# htu20df.net
KiCad netlist of a schematic drawn in EAGLE
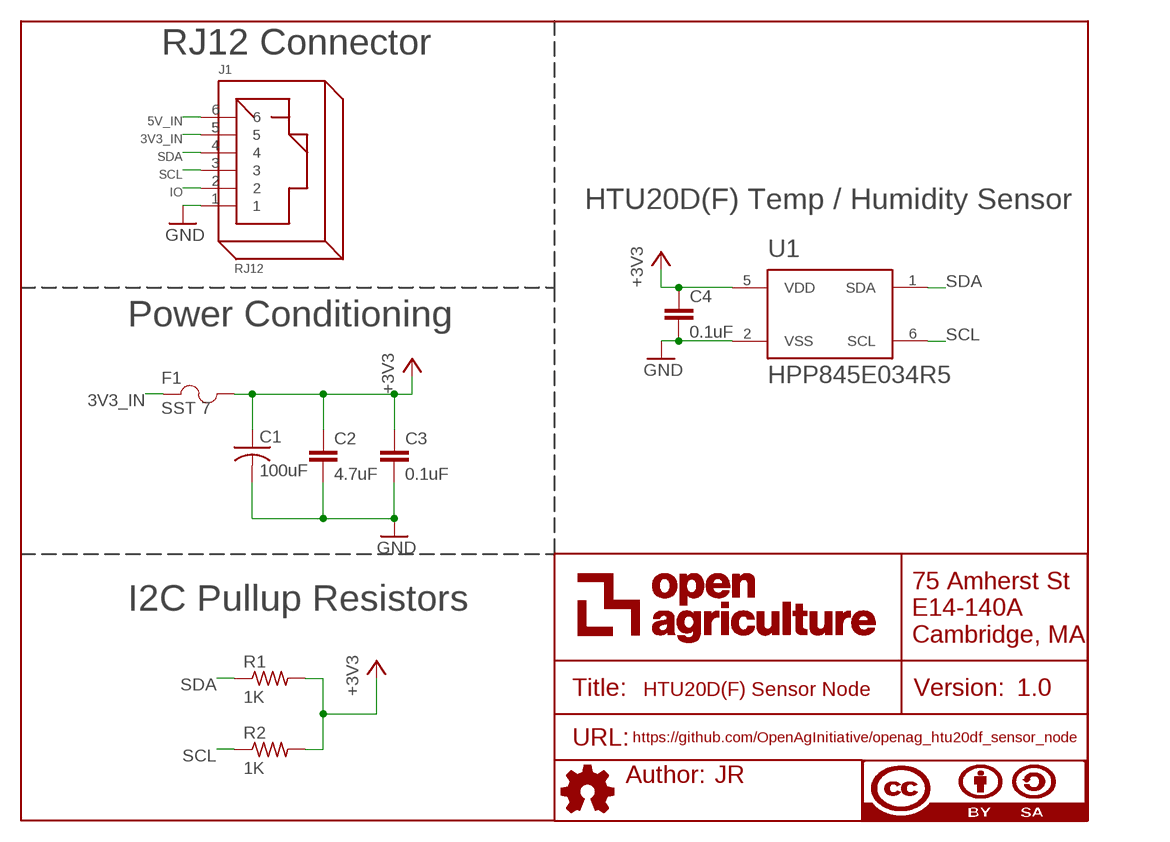
[diagram p0: schematic, sheet 1]

(export (version "E")
  (design (tool "Eeschema 10.0.6"))
  (components
    (comp (ref "C1")
      (value "100uF")
      (footprint "eagle-import:EEE-1HA101UP")
      (libsource (lib "eagle-import") (part "100UF-EEE-1HA101UP"))
    )
    (comp (ref "C2")
      (value "4.7uF")
      (footprint "eagle-import:C0805")
      (libsource (lib "eagle-import") (part "4.7UF-CL21A475KBQNNNE"))
    )
    (comp (ref "C3")
      (value "0.1uF")
      (footprint "eagle-import:C0603")
      (libsource (lib "eagle-import") (part "0.1UF-C0603C104K5RACTU"))
    )
    (comp (ref "C4")
      (value "0.1uF")
      (footprint "eagle-import:C0603")
      (libsource (lib "eagle-import") (part "0.1UF-C0603C104K5RACTU"))
    )
    (comp (ref "F1")
      (value "SST 7")
      (footprint "eagle-import:SS")
      (libsource (lib "eagle-import") (part "SST_7"))
    )
    (comp (ref "FRAME1")
      (value "DOCFIELD")
      (footprint "eagle-import:DOCFIELD")
      (fields
        (field (name "TITLE") "Example Template")
        (field (name "AUTHOR") "XX")
        (field (name "VER") "1.0")
        (field (name "URL") "https://github.com/OpenAgInitiative/openag_eagle_template")
        (field (name "AUTHOR_1") "JR")
        (field (name "TITLE_1") "HTU20D(F) Sensor Node")
        (field (name "URL_1") "https://github.com/OpenAgInitiative/openag_htu20df_sensor_node")
      )
      (libsource (lib "eagle-import") (part "DOCFIELD"))
    )
    (comp (ref "J1")
      (value "RJ12")
      (footprint "eagle-import:RJ12")
      (libsource (lib "eagle-import") (part "A-2004-1-4-LP-N-R"))
    )
    (comp (ref "R1")
      (value "1K")
      (footprint "eagle-import:RC0603N")
      (libsource (lib "eagle-import") (part "1K-ERJ-PB3D1001V"))
    )
    (comp (ref "R2")
      (value "1K")
      (footprint "eagle-import:RC0603N")
      (libsource (lib "eagle-import") (part "1K-ERJ-PB3D1001V"))
    )
    (comp (ref "U1")
      (value "HPP845E034R5")
      (footprint "eagle-import:HTU20D(F)")
      (libsource (lib "eagle-import") (part "HPP845E034R5"))
    )
  )
  (nets
    (net (code "1") (name "+3V3") (class "Default")
      (node (ref "C1") (pin "+") (pinfunction "1(+)_+") (pintype "passive"))
      (node (ref "C2") (pin "1") (pinfunction "1_1") (pintype "passive"))
      (node (ref "C3") (pin "1") (pinfunction "1_1") (pintype "passive"))
      (node (ref "C4") (pin "1") (pinfunction "1_1") (pintype "passive"))
      (node (ref "F1") (pin "2") (pinfunction "2_2") (pintype "passive"))
      (node (ref "R1") (pin "2") (pinfunction "2_2") (pintype "passive"))
      (node (ref "R2") (pin "2") (pinfunction "2_2") (pintype "passive"))
      (node (ref "U1") (pin "5") (pinfunction "VDD_5") (pintype "power_in"))
    )
    (net (code "2") (name "3V3_IN") (class "Default")
      (node (ref "F1") (pin "1") (pinfunction "1_1") (pintype "passive"))
      (node (ref "J1") (pin "5") (pinfunction "5_5") (pintype "bidirectional"))
    )
    (net (code "3") (name "5V_IN") (class "Default")
      (node (ref "J1") (pin "6") (pinfunction "6_6") (pintype "bidirectional"))
    )
    (net (code "4") (name "GND") (class "Default")
      (node (ref "C1") (pin "-") (pinfunction "2(-)_-") (pintype "passive"))
      (node (ref "C2") (pin "2") (pinfunction "2_2") (pintype "passive"))
      (node (ref "C3") (pin "2") (pinfunction "2_2") (pintype "passive"))
      (node (ref "C4") (pin "2") (pinfunction "2_2") (pintype "passive"))
      (node (ref "J1") (pin "1") (pinfunction "1_1") (pintype "bidirectional"))
      (node (ref "U1") (pin "2") (pinfunction "VSS_2") (pintype "power_in"))
    )
    (net (code "5") (name "IO") (class "Default")
      (node (ref "J1") (pin "2") (pinfunction "2_2") (pintype "bidirectional"))
    )
    (net (code "6") (name "SCL") (class "Default")
      (node (ref "J1") (pin "3") (pinfunction "3_3") (pintype "bidirectional"))
      (node (ref "R2") (pin "1") (pinfunction "1_1") (pintype "passive"))
      (node (ref "U1") (pin "6") (pinfunction "SCL_6") (pintype "bidirectional"))
    )
    (net (code "7") (name "SDA") (class "Default")
      (node (ref "J1") (pin "4") (pinfunction "4_4") (pintype "bidirectional"))
      (node (ref "R1") (pin "1") (pinfunction "1_1") (pintype "passive"))
      (node (ref "U1") (pin "1") (pinfunction "SDA_1") (pintype "bidirectional"))
    )
  )
)
